# onStep-board-power.net
KiCad netlist of a schematic drawn in Altium Designer
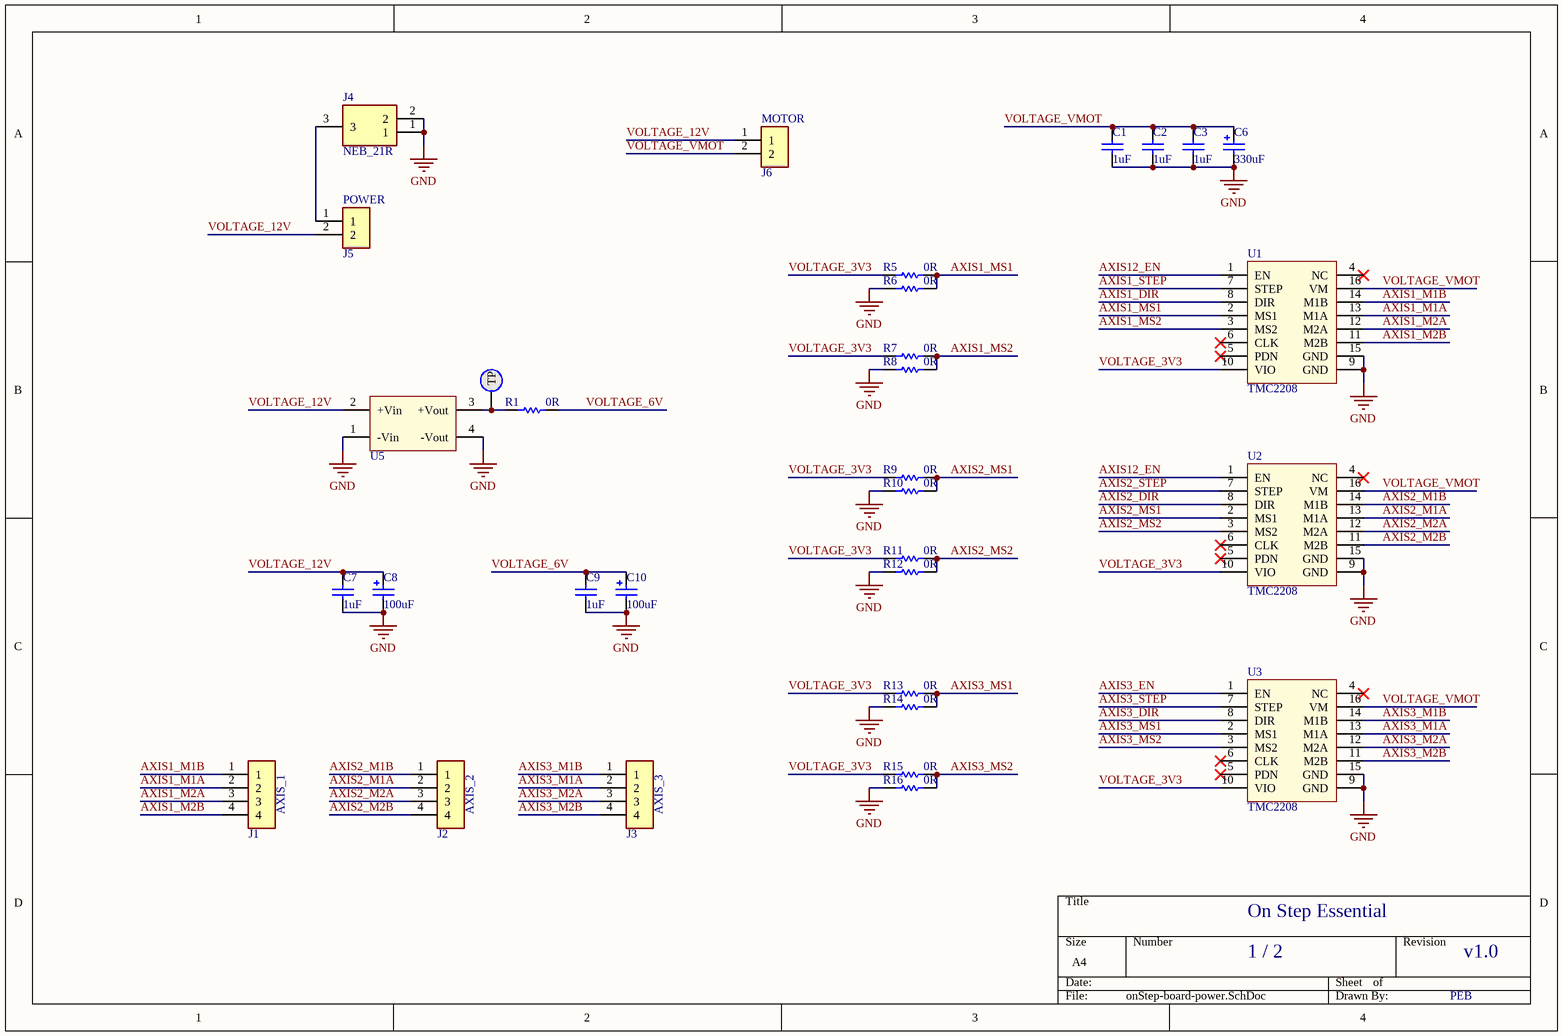
[diagram p0: onStep-board-power.SchDoc]

(export (version "E")
  (design (tool "Eeschema 10.0.6"))
  (components
    (comp (ref "C1")
      (value "1uF")
      (footprint "0805")
      (description "Capacitor")
      (fields (field (name "Comment") "Cap") (field (name "PUBLISHER") "Altium Limited"))
      (libsource (lib "Miscellaneous Devices") (part "Cap"))
    )
    (comp (ref "C2")
      (value "1uF")
      (footprint "0805")
      (description "Capacitor")
      (fields (field (name "Comment") "Cap") (field (name "PUBLISHER") "Altium Limited"))
      (libsource (lib "Miscellaneous Devices") (part "Cap"))
    )
    (comp (ref "C3")
      (value "1uF")
      (footprint "0805")
      (description "Capacitor")
      (fields (field (name "Comment") "Cap") (field (name "PUBLISHER") "Altium Limited"))
      (libsource (lib "Miscellaneous Devices") (part "Cap"))
    )
    (comp (ref "C6")
      (value "330uF")
      (footprint "WCAP-ASLL_8x10.5")
      (description "WCAP-ASLL Aluminum Electrolytic Capacitors, size Ф8x10.5mm, 25V DC, 330uF")
      (fields (field (name "PART NUMBER") "865060453008") (field (name "PUBLISHER") "Wurth Elektronik"))
      (libsource (lib "ALTIUM-WCAP-ASLL-rev17a") (part "865060453008"))
    )
    (comp (ref "C7")
      (value "1uF")
      (footprint "0805")
      (description "Capacitor")
      (fields (field (name "Comment") "Cap") (field (name "PUBLISHER") "Altium Limited"))
      (libsource (lib "Miscellaneous Devices") (part "Cap"))
    )
    (comp (ref "C8")
      (value "100uF")
      (footprint "WCAP-ASLL_8x10.5")
      (description "WCAP-ASLL Aluminum Electrolytic Capacitors, size Ф8x10.5mm, 25V DC, 150uF")
      (fields (field (name "PART NUMBER") "865060453006") (field (name "PUBLISHER") "Wurth Elektronik"))
      (libsource (lib "ALTIUM-WCAP-ASLL-rev17a") (part "865060453006"))
    )
    (comp (ref "C9")
      (value "1uF")
      (footprint "0805")
      (description "Capacitor")
      (fields (field (name "Comment") "Cap") (field (name "PUBLISHER") "Altium Limited"))
      (libsource (lib "Miscellaneous Devices") (part "Cap"))
    )
    (comp (ref "C10")
      (value "100uF")
      (footprint "WCAP-ASLL_8x10.5")
      (description "WCAP-ASLL Aluminum Electrolytic Capacitors, size Ф8x10.5mm, 25V DC, 150uF")
      (fields (field (name "PART NUMBER") "865060453006") (field (name "PUBLISHER") "Wurth Elektronik"))
      (libsource (lib "ALTIUM-WCAP-ASLL-rev17a") (part "865060453006"))
    )
    (comp (ref "J1")
      (value "AXIS_1")
      (footprint "lib_common:B4BXHALFSN")
      (description "Connector")
      (fields (field (name "MANUFACTURER_PART_NUMBER") "B4B-XH-A(LF)(SN)"))
      (libsource (lib "lib_common") (part "B4B-XH-A_LF__SN_"))
    )
    (comp (ref "J2")
      (value "AXIS_2")
      (footprint "lib_common:B4BXHALFSN")
      (description "Connector")
      (fields (field (name "MANUFACTURER_PART_NUMBER") "B4B-XH-A(LF)(SN)"))
      (libsource (lib "lib_common") (part "B4B-XH-A_LF__SN_"))
    )
    (comp (ref "J3")
      (value "AXIS_3")
      (footprint "lib_common:B4BXHALFSN")
      (description "Connector")
      (fields (field (name "MANUFACTURER_PART_NUMBER") "B4B-XH-A(LF)(SN)"))
      (libsource (lib "lib_common") (part "B4B-XH-A_LF__SN_"))
    )
    (comp (ref "J4")
      (value "NEB_21R")
      (footprint "lib_common:NEB21R")
      (description "Connector")
      (fields (field (name "MANUFACTURER_PART_NUMBER") "NEB+21+R"))
      (libsource (lib "lib_common") (part "NEB_21R"))
    )
    (comp (ref "J5")
      (value "POWER")
      (footprint "lib_common:B2BXHALFSN")
      (description "Connector")
      (fields (field (name "MANUFACTURER_PART_NUMBER") "B2B-XH-A(LF)(SN)"))
      (libsource (lib "lib_common") (part "B2B-XH-A_LF__SN_"))
    )
    (comp (ref "J6")
      (value "MOTOR")
      (footprint "lib_common:B2BXHALFSN")
      (description "Connector")
      (fields (field (name "MANUFACTURER_PART_NUMBER") "B2B-XH-A(LF)(SN)"))
      (libsource (lib "lib_common") (part "B2B-XH-A_LF__SN_"))
    )
    (comp (ref "R1")
      (value "0R")
      (footprint "0805")
      (description "Resistor")
      (fields (field (name "Comment") "Res1") (field (name "PUBLISHER") "Altium Limited"))
      (libsource (lib "Miscellaneous Devices") (part "Res1"))
    )
    (comp (ref "R5")
      (value "0R")
      (footprint "0805")
      (description "Resistor")
      (fields (field (name "Comment") "Res1") (field (name "PUBLISHER") "Altium Limited"))
      (libsource (lib "Miscellaneous Devices") (part "Res1"))
    )
    (comp (ref "R6")
      (value "0R")
      (footprint "0805")
      (description "Resistor")
      (fields (field (name "Comment") "Res1") (field (name "PUBLISHER") "Altium Limited"))
      (libsource (lib "Miscellaneous Devices") (part "Res1"))
    )
    (comp (ref "R7")
      (value "0R")
      (footprint "0805")
      (description "Resistor")
      (fields (field (name "Comment") "Res1") (field (name "PUBLISHER") "Altium Limited"))
      (libsource (lib "Miscellaneous Devices") (part "Res1"))
    )
    (comp (ref "R8")
      (value "0R")
      (footprint "0805")
      (description "Resistor")
      (fields (field (name "Comment") "Res1") (field (name "PUBLISHER") "Altium Limited"))
      (libsource (lib "Miscellaneous Devices") (part "Res1"))
    )
    (comp (ref "R9")
      (value "0R")
      (footprint "0805")
      (description "Resistor")
      (fields (field (name "Comment") "Res1") (field (name "PUBLISHER") "Altium Limited"))
      (libsource (lib "Miscellaneous Devices") (part "Res1"))
    )
    (comp (ref "R10")
      (value "0R")
      (footprint "0805")
      (description "Resistor")
      (fields (field (name "Comment") "Res1") (field (name "PUBLISHER") "Altium Limited"))
      (libsource (lib "Miscellaneous Devices") (part "Res1"))
    )
    (comp (ref "R11")
      (value "0R")
      (footprint "0805")
      (description "Resistor")
      (fields (field (name "Comment") "Res1") (field (name "PUBLISHER") "Altium Limited"))
      (libsource (lib "Miscellaneous Devices") (part "Res1"))
    )
    (comp (ref "R12")
      (value "0R")
      (footprint "0805")
      (description "Resistor")
      (fields (field (name "Comment") "Res1") (field (name "PUBLISHER") "Altium Limited"))
      (libsource (lib "Miscellaneous Devices") (part "Res1"))
    )
    (comp (ref "R13")
      (value "0R")
      (footprint "0805")
      (description "Resistor")
      (fields (field (name "Comment") "Res1") (field (name "PUBLISHER") "Altium Limited"))
      (libsource (lib "Miscellaneous Devices") (part "Res1"))
    )
    (comp (ref "R14")
      (value "0R")
      (footprint "0805")
      (description "Resistor")
      (fields (field (name "Comment") "Res1") (field (name "PUBLISHER") "Altium Limited"))
      (libsource (lib "Miscellaneous Devices") (part "Res1"))
    )
    (comp (ref "R15")
      (value "0R")
      (footprint "0805")
      (description "Resistor")
      (fields (field (name "Comment") "Res1") (field (name "PUBLISHER") "Altium Limited"))
      (libsource (lib "Miscellaneous Devices") (part "Res1"))
    )
    (comp (ref "R16")
      (value "0R")
      (footprint "0805")
      (description "Resistor")
      (fields (field (name "Comment") "Res1") (field (name "PUBLISHER") "Altium Limited"))
      (libsource (lib "Miscellaneous Devices") (part "Res1"))
    )
    (comp (ref "TP1")
      (value "TEST_POINT")
      (footprint "TEST_POINT")
      (libsource (lib "lib_common") (part "TEST_POINT"))
    )
    (comp (ref "U1") (value "TMC2208") (footprint "TMC22xx") (libsource (lib "lib_common") (part "TMC2208")))
    (comp (ref "U2") (value "TMC2208") (footprint "TMC22xx") (libsource (lib "lib_common") (part "TMC2208")))
    (comp (ref "U3") (value "TMC2208") (footprint "TMC22xx") (libsource (lib "lib_common") (part "TMC2208")))
    (comp (ref "U5")
      (value "DCDC-MINI360")
      (footprint "DCDC-MINI360")
      (libsource (lib "lib_common") (part "DCDC-MINI360"))
    )
  )
  (nets
    (net (code "1") (name "/AXIS1_DIR") (class "Default")
      (node (ref "U1") (pin "8") (pinfunction "DIR_8") (pintype "passive"))
    )
    (net (code "2") (name "/AXIS1_M1A") (class "Default")
      (node (ref "J1") (pin "2") (pinfunction "2_2") (pintype "passive"))
      (node (ref "U1") (pin "13") (pinfunction "M1A_13") (pintype "passive"))
    )
    (net (code "3") (name "/AXIS1_M1B") (class "Default")
      (node (ref "J1") (pin "1") (pinfunction "1_1") (pintype "passive"))
      (node (ref "U1") (pin "14") (pinfunction "M1B_14") (pintype "passive"))
    )
    (net (code "4") (name "/AXIS1_M2A") (class "Default")
      (node (ref "J1") (pin "3") (pinfunction "3_3") (pintype "passive"))
      (node (ref "U1") (pin "12") (pinfunction "M2A_12") (pintype "passive"))
    )
    (net (code "5") (name "/AXIS1_M2B") (class "Default")
      (node (ref "J1") (pin "4") (pinfunction "4_4") (pintype "passive"))
      (node (ref "U1") (pin "11") (pinfunction "M2B_11") (pintype "passive"))
    )
    (net (code "6") (name "/AXIS1_MS1") (class "Default")
      (node (ref "R5") (pin "2") (pinfunction "2_2") (pintype "passive"))
      (node (ref "R6") (pin "2") (pinfunction "2_2") (pintype "passive"))
      (node (ref "U1") (pin "2") (pinfunction "MS1_2") (pintype "passive"))
    )
    (net (code "7") (name "/AXIS1_MS2") (class "Default")
      (node (ref "R7") (pin "2") (pinfunction "2_2") (pintype "passive"))
      (node (ref "R8") (pin "2") (pinfunction "2_2") (pintype "passive"))
      (node (ref "U1") (pin "3") (pinfunction "MS2_3") (pintype "passive"))
    )
    (net (code "8") (name "/AXIS1_STEP") (class "Default")
      (node (ref "U1") (pin "7") (pinfunction "STEP_7") (pintype "passive"))
    )
    (net (code "9") (name "/AXIS2_DIR") (class "Default")
      (node (ref "U2") (pin "8") (pinfunction "DIR_8") (pintype "passive"))
    )
    (net (code "10") (name "/AXIS2_M1A") (class "Default")
      (node (ref "J2") (pin "2") (pinfunction "2_2") (pintype "passive"))
      (node (ref "U2") (pin "13") (pinfunction "M1A_13") (pintype "passive"))
    )
    (net (code "11") (name "/AXIS2_M1B") (class "Default")
      (node (ref "J2") (pin "1") (pinfunction "1_1") (pintype "passive"))
      (node (ref "U2") (pin "14") (pinfunction "M1B_14") (pintype "passive"))
    )
    (net (code "12") (name "/AXIS2_M2A") (class "Default")
      (node (ref "J2") (pin "3") (pinfunction "3_3") (pintype "passive"))
      (node (ref "U2") (pin "12") (pinfunction "M2A_12") (pintype "passive"))
    )
    (net (code "13") (name "/AXIS2_M2B") (class "Default")
      (node (ref "J2") (pin "4") (pinfunction "4_4") (pintype "passive"))
      (node (ref "U2") (pin "11") (pinfunction "M2B_11") (pintype "passive"))
    )
    (net (code "14") (name "/AXIS2_MS1") (class "Default")
      (node (ref "R10") (pin "2") (pinfunction "2_2") (pintype "passive"))
      (node (ref "R9") (pin "2") (pinfunction "2_2") (pintype "passive"))
      (node (ref "U2") (pin "2") (pinfunction "MS1_2") (pintype "passive"))
    )
    (net (code "15") (name "/AXIS2_MS2") (class "Default")
      (node (ref "R11") (pin "2") (pinfunction "2_2") (pintype "passive"))
      (node (ref "R12") (pin "2") (pinfunction "2_2") (pintype "passive"))
      (node (ref "U2") (pin "3") (pinfunction "MS2_3") (pintype "passive"))
    )
    (net (code "16") (name "/AXIS2_STEP") (class "Default")
      (node (ref "U2") (pin "7") (pinfunction "STEP_7") (pintype "passive"))
    )
    (net (code "17") (name "/AXIS3_DIR") (class "Default")
      (node (ref "U3") (pin "8") (pinfunction "DIR_8") (pintype "passive"))
    )
    (net (code "18") (name "/AXIS3_EN") (class "Default")
      (node (ref "U3") (pin "1") (pinfunction "EN_1") (pintype "passive"))
    )
    (net (code "19") (name "/AXIS3_M1A") (class "Default")
      (node (ref "J3") (pin "2") (pinfunction "2_2") (pintype "passive"))
      (node (ref "U3") (pin "13") (pinfunction "M1A_13") (pintype "passive"))
    )
    (net (code "20") (name "/AXIS3_M1B") (class "Default")
      (node (ref "J3") (pin "1") (pinfunction "1_1") (pintype "passive"))
      (node (ref "U3") (pin "14") (pinfunction "M1B_14") (pintype "passive"))
    )
    (net (code "21") (name "/AXIS3_M2A") (class "Default")
      (node (ref "J3") (pin "3") (pinfunction "3_3") (pintype "passive"))
      (node (ref "U3") (pin "12") (pinfunction "M2A_12") (pintype "passive"))
    )
    (net (code "22") (name "/AXIS3_M2B") (class "Default")
      (node (ref "J3") (pin "4") (pinfunction "4_4") (pintype "passive"))
      (node (ref "U3") (pin "11") (pinfunction "M2B_11") (pintype "passive"))
    )
    (net (code "23") (name "/AXIS3_MS1") (class "Default")
      (node (ref "R13") (pin "2") (pinfunction "2_2") (pintype "passive"))
      (node (ref "R14") (pin "2") (pinfunction "2_2") (pintype "passive"))
      (node (ref "U3") (pin "2") (pinfunction "MS1_2") (pintype "passive"))
    )
    (net (code "24") (name "/AXIS3_MS2") (class "Default")
      (node (ref "R15") (pin "2") (pinfunction "2_2") (pintype "passive"))
      (node (ref "R16") (pin "2") (pinfunction "2_2") (pintype "passive"))
      (node (ref "U3") (pin "3") (pinfunction "MS2_3") (pintype "passive"))
    )
    (net (code "25") (name "/AXIS3_STEP") (class "Default")
      (node (ref "U3") (pin "7") (pinfunction "STEP_7") (pintype "passive"))
    )
    (net (code "26") (name "/AXIS12_EN") (class "Default")
      (node (ref "U1") (pin "1") (pinfunction "EN_1") (pintype "passive"))
      (node (ref "U2") (pin "1") (pinfunction "EN_1") (pintype "passive"))
    )
    (net (code "27") (name "/VOLTAGE_3V3") (class "Default")
      (node (ref "R11") (pin "1") (pinfunction "1_1") (pintype "passive"))
      (node (ref "R13") (pin "1") (pinfunction "1_1") (pintype "passive"))
      (node (ref "R15") (pin "1") (pinfunction "1_1") (pintype "passive"))
      (node (ref "R5") (pin "1") (pinfunction "1_1") (pintype "passive"))
      (node (ref "R7") (pin "1") (pinfunction "1_1") (pintype "passive"))
      (node (ref "R9") (pin "1") (pinfunction "1_1") (pintype "passive"))
      (node (ref "U1") (pin "10") (pinfunction "VIO_10") (pintype "passive"))
      (node (ref "U2") (pin "10") (pinfunction "VIO_10") (pintype "passive"))
      (node (ref "U3") (pin "10") (pinfunction "VIO_10") (pintype "passive"))
    )
    (net (code "28") (name "/VOLTAGE_6V") (class "Default")
      (node (ref "C10") (pin "1") (pinfunction "P_1") (pintype "passive"))
      (node (ref "C9") (pin "2") (pinfunction "2_2") (pintype "passive"))
      (node (ref "R1") (pin "2") (pinfunction "2_2") (pintype "passive"))
    )
    (net (code "29") (name "/VOLTAGE_12V") (class "Default")
      (node (ref "C7") (pin "2") (pinfunction "2_2") (pintype "passive"))
      (node (ref "C8") (pin "1") (pinfunction "P_1") (pintype "passive"))
      (node (ref "J5") (pin "2") (pinfunction "2_2") (pintype "passive"))
      (node (ref "J6") (pin "1") (pinfunction "1_1") (pintype "passive"))
      (node (ref "U5") (pin "2") (pinfunction "+Vin_2") (pintype "passive"))
    )
    (net (code "30") (name "/VOLTAGE_VMOT") (class "Default")
      (node (ref "C1") (pin "2") (pinfunction "2_2") (pintype "passive"))
      (node (ref "C2") (pin "2") (pinfunction "2_2") (pintype "passive"))
      (node (ref "C3") (pin "2") (pinfunction "2_2") (pintype "passive"))
      (node (ref "C6") (pin "1") (pinfunction "P_1") (pintype "passive"))
      (node (ref "J6") (pin "2") (pinfunction "2_2") (pintype "passive"))
      (node (ref "U1") (pin "16") (pinfunction "VM_16") (pintype "passive"))
      (node (ref "U2") (pin "16") (pinfunction "VM_16") (pintype "passive"))
      (node (ref "U3") (pin "16") (pinfunction "VM_16") (pintype "passive"))
    )
    (net (code "31") (name "GND") (class "Default")
      (node (ref "C1") (pin "1") (pinfunction "1_1") (pintype "passive"))
      (node (ref "C10") (pin "2") (pinfunction "N_2") (pintype "passive"))
      (node (ref "C2") (pin "1") (pinfunction "1_1") (pintype "passive"))
      (node (ref "C3") (pin "1") (pinfunction "1_1") (pintype "passive"))
      (node (ref "C6") (pin "2") (pinfunction "N_2") (pintype "passive"))
      (node (ref "C7") (pin "1") (pinfunction "1_1") (pintype "passive"))
      (node (ref "C8") (pin "2") (pinfunction "N_2") (pintype "passive"))
      (node (ref "C9") (pin "1") (pinfunction "1_1") (pintype "passive"))
      (node (ref "J4") (pin "1") (pinfunction "1_1") (pintype "passive"))
      (node (ref "J4") (pin "2") (pinfunction "2_2") (pintype "passive"))
      (node (ref "R10") (pin "1") (pinfunction "1_1") (pintype "passive"))
      (node (ref "R12") (pin "1") (pinfunction "1_1") (pintype "passive"))
      (node (ref "R14") (pin "1") (pinfunction "1_1") (pintype "passive"))
      (node (ref "R16") (pin "1") (pinfunction "1_1") (pintype "passive"))
      (node (ref "R6") (pin "1") (pinfunction "1_1") (pintype "passive"))
      (node (ref "R8") (pin "1") (pinfunction "1_1") (pintype "passive"))
      (node (ref "U1") (pin "15") (pinfunction "GND_15") (pintype "passive"))
      (node (ref "U1") (pin "9") (pinfunction "GND_9") (pintype "passive"))
      (node (ref "U2") (pin "15") (pinfunction "GND_15") (pintype "passive"))
      (node (ref "U2") (pin "9") (pinfunction "GND_9") (pintype "passive"))
      (node (ref "U3") (pin "15") (pinfunction "GND_15") (pintype "passive"))
      (node (ref "U3") (pin "9") (pinfunction "GND_9") (pintype "passive"))
      (node (ref "U5") (pin "1") (pinfunction "-Vin_1") (pintype "passive"))
      (node (ref "U5") (pin "4") (pinfunction "-Vout_4") (pintype "passive"))
    )
    (net (code "32") (name "Net-(J4-Pad3)") (class "Default")
      (node (ref "J4") (pin "3") (pinfunction "3_3") (pintype "passive"))
      (node (ref "J5") (pin "1") (pinfunction "1_1") (pintype "passive"))
    )
    (net (code "33") (name "Net-(TP1-TP)") (class "Default")
      (node (ref "R1") (pin "1") (pinfunction "1_1") (pintype "passive"))
      (node (ref "TP1") (pin "1") (pinfunction "TP_1") (pintype "passive"))
      (node (ref "U5") (pin "3") (pinfunction "+Vout_3") (pintype "passive"))
    )
    (net (code "34") (name "unconnected-(U1-CLK-Pad6)") (class "Default")
      (node (ref "U1") (pin "6") (pinfunction "CLK_6") (pintype "passive+no_connect"))
    )
    (net (code "35") (name "unconnected-(U1-NC-Pad4)") (class "Default")
      (node (ref "U1") (pin "4") (pinfunction "NC_4") (pintype "passive+no_connect"))
    )
    (net (code "36") (name "unconnected-(U1-PDN-Pad5)") (class "Default")
      (node (ref "U1") (pin "5") (pinfunction "PDN_5") (pintype "passive+no_connect"))
    )
    (net (code "37") (name "unconnected-(U2-CLK-Pad6)") (class "Default")
      (node (ref "U2") (pin "6") (pinfunction "CLK_6") (pintype "passive+no_connect"))
    )
    (net (code "38") (name "unconnected-(U2-NC-Pad4)") (class "Default")
      (node (ref "U2") (pin "4") (pinfunction "NC_4") (pintype "passive+no_connect"))
    )
    (net (code "39") (name "unconnected-(U2-PDN-Pad5)") (class "Default")
      (node (ref "U2") (pin "5") (pinfunction "PDN_5") (pintype "passive+no_connect"))
    )
    (net (code "40") (name "unconnected-(U3-CLK-Pad6)") (class "Default")
      (node (ref "U3") (pin "6") (pinfunction "CLK_6") (pintype "passive+no_connect"))
    )
    (net (code "41") (name "unconnected-(U3-NC-Pad4)") (class "Default")
      (node (ref "U3") (pin "4") (pinfunction "NC_4") (pintype "passive+no_connect"))
    )
    (net (code "42") (name "unconnected-(U3-PDN-Pad5)") (class "Default")
      (node (ref "U3") (pin "5") (pinfunction "PDN_5") (pintype "passive+no_connect"))
    )
  )
)
